# main_board.net
KiCad netlist of a schematic drawn in EAGLE
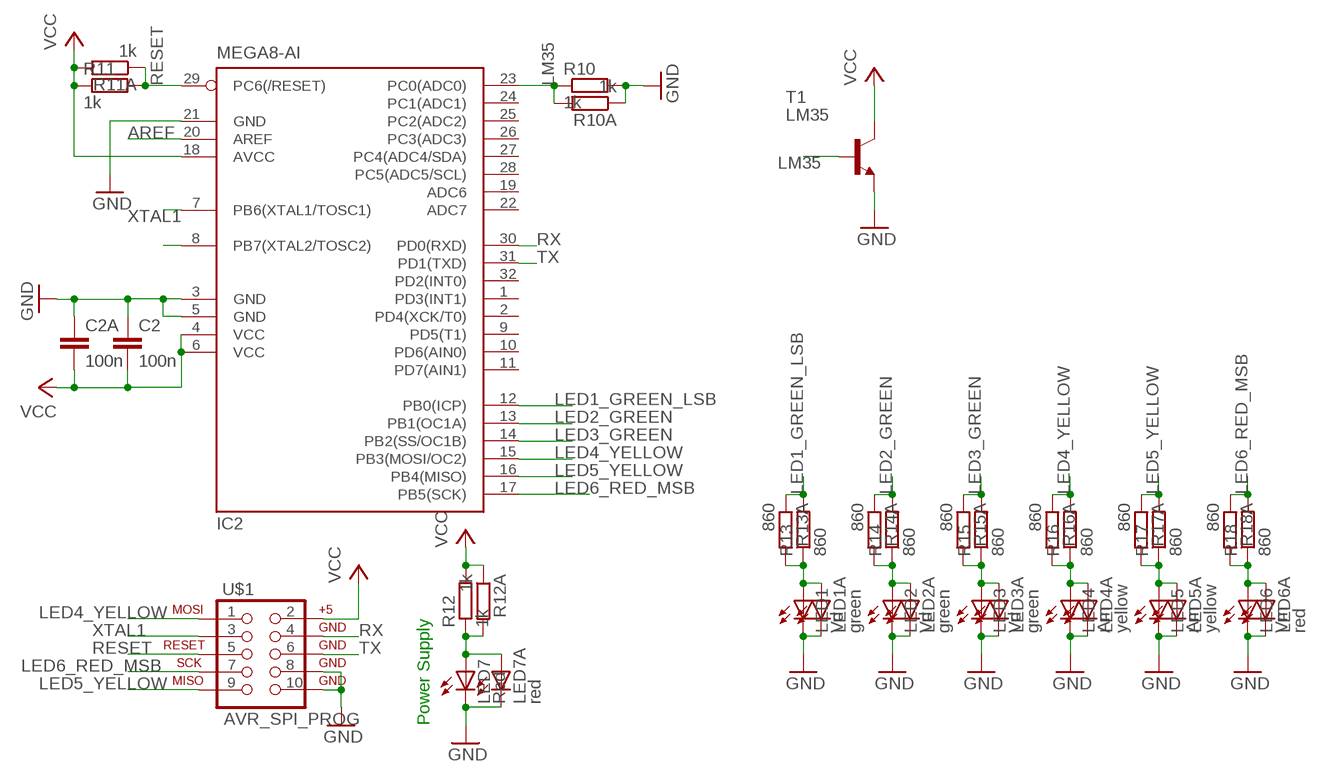
[diagram p0: schematic, sheet 1]

(export (version "E")
  (design (tool "Eeschema 10.0.6"))
  (components
    (comp (ref "C2")
      (value "100n")
      (footprint "eagle-import:C5B3")
      (libsource (lib "eagle-import") (part "C5/3"))
    )
    (comp (ref "C2A")
      (value "100n")
      (footprint "eagle-import:C0805")
      (libsource (lib "eagle-import") (part "C-EUC0805"))
    )
    (comp (ref "IC2")
      (value "MEGA8-AI")
      (footprint "eagle-import:TQFP32-08")
      (fields (field (name "MPN") "ATMEGA8-16AU"))
      (libsource (lib "eagle-import") (part "MEGA8-AI"))
    )
    (comp (ref "LED1")
      (value "Vd")
      (footprint "eagle-import:LED3MM")
      (libsource (lib "eagle-import") (part "LED3MM"))
    )
    (comp (ref "LED1A")
      (value "green")
      (footprint "eagle-import:CHIP-LED0805")
      (libsource (lib "eagle-import") (part "LEDCHIP-LED0805"))
    )
    (comp (ref "LED2")
      (value "Vd")
      (footprint "eagle-import:LED3MM")
      (libsource (lib "eagle-import") (part "LED3MM"))
    )
    (comp (ref "LED2A")
      (value "green")
      (footprint "eagle-import:CHIP-LED0805")
      (libsource (lib "eagle-import") (part "LEDCHIP-LED0805"))
    )
    (comp (ref "LED3")
      (value "Vd")
      (footprint "eagle-import:LED3MM")
      (libsource (lib "eagle-import") (part "LED3MM"))
    )
    (comp (ref "LED3A")
      (value "green")
      (footprint "eagle-import:CHIP-LED0805")
      (libsource (lib "eagle-import") (part "LEDCHIP-LED0805"))
    )
    (comp (ref "LED4")
      (value "Am")
      (footprint "eagle-import:LED3MM")
      (libsource (lib "eagle-import") (part "LED3MM"))
    )
    (comp (ref "LED4A")
      (value "yellow")
      (footprint "eagle-import:CHIP-LED0805")
      (libsource (lib "eagle-import") (part "LEDCHIP-LED0805"))
    )
    (comp (ref "LED5")
      (value "Am")
      (footprint "eagle-import:LED3MM")
      (libsource (lib "eagle-import") (part "LED3MM"))
    )
    (comp (ref "LED5A")
      (value "yellow")
      (footprint "eagle-import:CHIP-LED0805")
      (libsource (lib "eagle-import") (part "LEDCHIP-LED0805"))
    )
    (comp (ref "LED6")
      (value "Vm")
      (footprint "eagle-import:LED3MM")
      (libsource (lib "eagle-import") (part "LED3MM"))
    )
    (comp (ref "LED6A")
      (value "red")
      (footprint "eagle-import:CHIP-LED0805")
      (libsource (lib "eagle-import") (part "LEDCHIP-LED0805"))
    )
    (comp (ref "LED7")
      (value "Red")
      (footprint "eagle-import:LED3MM")
      (libsource (lib "eagle-import") (part "LED3MM"))
    )
    (comp (ref "LED7A")
      (value "red")
      (footprint "eagle-import:CHIP-LED0805")
      (libsource (lib "eagle-import") (part "LEDCHIP-LED0805"))
    )
    (comp (ref "R10")
      (value "1k")
      (footprint "eagle-import:0207_10")
      (libsource (lib "eagle-import") (part "resistor_R-EU_0207/10"))
    )
    (comp (ref "R10A")
      (value "1k")
      (footprint "eagle-import:M0805")
      (libsource (lib "eagle-import") (part "R-EU_M0805"))
    )
    (comp (ref "R11")
      (value "1k")
      (footprint "eagle-import:0207_10")
      (libsource (lib "eagle-import") (part "resistor_R-EU_0207/10"))
    )
    (comp (ref "R11A")
      (value "1k")
      (footprint "eagle-import:M0805")
      (libsource (lib "eagle-import") (part "R-EU_M0805"))
    )
    (comp (ref "R12")
      (value "1k")
      (footprint "eagle-import:0207_10")
      (libsource (lib "eagle-import") (part "resistor_R-EU_0207/10"))
    )
    (comp (ref "R12A")
      (value "1k")
      (footprint "eagle-import:M0805")
      (libsource (lib "eagle-import") (part "R-EU_M0805"))
    )
    (comp (ref "R13")
      (value "860")
      (footprint "eagle-import:0207_10")
      (libsource (lib "eagle-import") (part "resistor_R-EU_0207/10"))
    )
    (comp (ref "R13A")
      (value "860")
      (footprint "eagle-import:M0805")
      (libsource (lib "eagle-import") (part "R-EU_M0805"))
    )
    (comp (ref "R14")
      (value "860")
      (footprint "eagle-import:0207_10")
      (libsource (lib "eagle-import") (part "resistor_R-EU_0207/10"))
    )
    (comp (ref "R14A")
      (value "860")
      (footprint "eagle-import:M0805")
      (libsource (lib "eagle-import") (part "R-EU_M0805"))
    )
    (comp (ref "R15")
      (value "860")
      (footprint "eagle-import:0207_10")
      (libsource (lib "eagle-import") (part "resistor_R-EU_0207/10"))
    )
    (comp (ref "R15A")
      (value "860")
      (footprint "eagle-import:M0805")
      (libsource (lib "eagle-import") (part "R-EU_M0805"))
    )
    (comp (ref "R16")
      (value "860")
      (footprint "eagle-import:0207_10")
      (libsource (lib "eagle-import") (part "resistor_R-EU_0207/10"))
    )
    (comp (ref "R16A")
      (value "860")
      (footprint "eagle-import:M0805")
      (libsource (lib "eagle-import") (part "R-EU_M0805"))
    )
    (comp (ref "R17")
      (value "860")
      (footprint "eagle-import:0207_10")
      (libsource (lib "eagle-import") (part "resistor_R-EU_0207/10"))
    )
    (comp (ref "R17A")
      (value "860")
      (footprint "eagle-import:M0805")
      (libsource (lib "eagle-import") (part "R-EU_M0805"))
    )
    (comp (ref "R18")
      (value "860")
      (footprint "eagle-import:0207_10")
      (libsource (lib "eagle-import") (part "resistor_R-EU_0207/10"))
    )
    (comp (ref "R18A")
      (value "860")
      (footprint "eagle-import:M0805")
      (libsource (lib "eagle-import") (part "R-EU_M0805"))
    )
    (comp (ref "T1")
      (value "LM35")
      (footprint "eagle-import:TO92-CBE")
      (libsource (lib "eagle-import") (part "-NPN-TO92-CBEMPS2222A"))
    )
    (comp (ref "U$1")
      (value "AVR_SPI_PROG")
      (footprint "eagle-import:AVR_ICSP")
      (libsource (lib "eagle-import") (part "AVR_SPI_PROG"))
    )
  )
  (nets
    (net (code "1") (name "/AREF") (class "Default")
      (node (ref "IC2") (pin "20") (pinfunction "AREF_20") (pintype "passive"))
    )
    (net (code "2") (name "/LED1_GREEN_LSB") (class "Default")
      (node (ref "IC2") (pin "12") (pinfunction "PB0(ICP)_12") (pintype "bidirectional"))
      (node (ref "R13") (pin "2") (pinfunction "2_2") (pintype "passive"))
      (node (ref "R13A") (pin "1") (pinfunction "1_1") (pintype "passive"))
    )
    (net (code "3") (name "/LED2_GREEN") (class "Default")
      (node (ref "IC2") (pin "13") (pinfunction "PB1(OC1A)_13") (pintype "bidirectional"))
      (node (ref "R14") (pin "2") (pinfunction "2_2") (pintype "passive"))
      (node (ref "R14A") (pin "1") (pinfunction "1_1") (pintype "passive"))
    )
    (net (code "4") (name "/LED3_GREEN") (class "Default")
      (node (ref "IC2") (pin "14") (pinfunction "PB2(SS/OC1B)_14") (pintype "bidirectional"))
      (node (ref "R15") (pin "2") (pinfunction "2_2") (pintype "passive"))
      (node (ref "R15A") (pin "1") (pinfunction "1_1") (pintype "passive"))
    )
    (net (code "5") (name "/LED4_YELLOW") (class "Default")
      (node (ref "IC2") (pin "15") (pinfunction "PB3(MOSI/OC2)_15") (pintype "bidirectional"))
      (node (ref "R16") (pin "2") (pinfunction "2_2") (pintype "passive"))
      (node (ref "R16A") (pin "1") (pinfunction "1_1") (pintype "passive"))
      (node (ref "U$1") (pin "1") (pinfunction "1_1") (pintype "passive"))
    )
    (net (code "6") (name "/LED5_YELLOW") (class "Default")
      (node (ref "IC2") (pin "16") (pinfunction "PB4(MISO)_16") (pintype "bidirectional"))
      (node (ref "R17") (pin "2") (pinfunction "2_2") (pintype "passive"))
      (node (ref "R17A") (pin "1") (pinfunction "1_1") (pintype "passive"))
      (node (ref "U$1") (pin "9") (pinfunction "9_9") (pintype "passive"))
    )
    (net (code "7") (name "/LED6_RED_MSB") (class "Default")
      (node (ref "IC2") (pin "17") (pinfunction "PB5(SCK)_17") (pintype "bidirectional"))
      (node (ref "R18") (pin "2") (pinfunction "2_2") (pintype "passive"))
      (node (ref "R18A") (pin "1") (pinfunction "1_1") (pintype "passive"))
      (node (ref "U$1") (pin "7") (pinfunction "7_7") (pintype "passive"))
    )
    (net (code "8") (name "/LM35") (class "Default")
      (node (ref "IC2") (pin "23") (pinfunction "PC0(ADC0)_23") (pintype "bidirectional"))
      (node (ref "R10") (pin "1") (pinfunction "1_1") (pintype "passive"))
      (node (ref "R10A") (pin "2") (pinfunction "2_2") (pintype "passive"))
      (node (ref "T1") (pin "B") (pinfunction "B_B") (pintype "passive"))
    )
    (net (code "9") (name "/RESET") (class "Default")
      (node (ref "IC2") (pin "29") (pinfunction "PC6(/RESET)_29") (pintype "bidirectional"))
      (node (ref "R11") (pin "2") (pinfunction "2_2") (pintype "passive"))
      (node (ref "R11A") (pin "1") (pinfunction "1_1") (pintype "passive"))
      (node (ref "U$1") (pin "5") (pinfunction "5_5") (pintype "passive"))
    )
    (net (code "10") (name "/RX") (class "Default")
      (node (ref "IC2") (pin "30") (pinfunction "PD0(RXD)_30") (pintype "bidirectional"))
      (node (ref "U$1") (pin "4") (pinfunction "4_4") (pintype "passive"))
    )
    (net (code "11") (name "/TX") (class "Default")
      (node (ref "IC2") (pin "31") (pinfunction "PD1(TXD)_31") (pintype "bidirectional"))
      (node (ref "U$1") (pin "6") (pinfunction "6_6") (pintype "passive"))
    )
    (net (code "12") (name "/XTAL1") (class "Default")
      (node (ref "IC2") (pin "7") (pinfunction "PB6(XTAL1/TOSC1)_7") (pintype "bidirectional"))
      (node (ref "U$1") (pin "3") (pinfunction "3_3") (pintype "passive"))
    )
    (net (code "13") (name "GND") (class "Default")
      (node (ref "C2") (pin "1") (pinfunction "1_1") (pintype "passive"))
      (node (ref "C2A") (pin "1") (pinfunction "1_1") (pintype "passive"))
      (node (ref "IC2") (pin "21") (pinfunction "GND_21") (pintype "power_in"))
      (node (ref "IC2") (pin "3") (pinfunction "GND_3") (pintype "power_in"))
      (node (ref "IC2") (pin "5") (pinfunction "GND_5") (pintype "power_in"))
      (node (ref "LED1") (pin "K") (pinfunction "C_K") (pintype "passive"))
      (node (ref "LED1A") (pin "C") (pinfunction "C_C") (pintype "passive"))
      (node (ref "LED2") (pin "K") (pinfunction "C_K") (pintype "passive"))
      (node (ref "LED2A") (pin "C") (pinfunction "C_C") (pintype "passive"))
      (node (ref "LED3") (pin "K") (pinfunction "C_K") (pintype "passive"))
      (node (ref "LED3A") (pin "C") (pinfunction "C_C") (pintype "passive"))
      (node (ref "LED4") (pin "K") (pinfunction "C_K") (pintype "passive"))
      (node (ref "LED4A") (pin "C") (pinfunction "C_C") (pintype "passive"))
      (node (ref "LED5") (pin "K") (pinfunction "C_K") (pintype "passive"))
      (node (ref "LED5A") (pin "C") (pinfunction "C_C") (pintype "passive"))
      (node (ref "LED6") (pin "K") (pinfunction "C_K") (pintype "passive"))
      (node (ref "LED6A") (pin "C") (pinfunction "C_C") (pintype "passive"))
      (node (ref "LED7") (pin "K") (pinfunction "C_K") (pintype "passive"))
      (node (ref "LED7A") (pin "C") (pinfunction "C_C") (pintype "passive"))
      (node (ref "R10") (pin "2") (pinfunction "2_2") (pintype "passive"))
      (node (ref "R10A") (pin "1") (pinfunction "1_1") (pintype "passive"))
      (node (ref "T1") (pin "E") (pinfunction "E_E") (pintype "passive"))
      (node (ref "U$1") (pin "10") (pinfunction "10_10") (pintype "passive"))
      (node (ref "U$1") (pin "8") (pinfunction "8_8") (pintype "passive"))
    )
    (net (code "14") (name "Net-(LED1-PadA)") (class "Default")
      (node (ref "LED1") (pin "A") (pinfunction "A_A") (pintype "passive"))
      (node (ref "LED1A") (pin "A") (pinfunction "A_A") (pintype "passive"))
      (node (ref "R13") (pin "1") (pinfunction "1_1") (pintype "passive"))
      (node (ref "R13A") (pin "2") (pinfunction "2_2") (pintype "passive"))
    )
    (net (code "15") (name "Net-(LED2-PadA)") (class "Default")
      (node (ref "LED2") (pin "A") (pinfunction "A_A") (pintype "passive"))
      (node (ref "LED2A") (pin "A") (pinfunction "A_A") (pintype "passive"))
      (node (ref "R14") (pin "1") (pinfunction "1_1") (pintype "passive"))
      (node (ref "R14A") (pin "2") (pinfunction "2_2") (pintype "passive"))
    )
    (net (code "16") (name "Net-(LED3-PadA)") (class "Default")
      (node (ref "LED3") (pin "A") (pinfunction "A_A") (pintype "passive"))
      (node (ref "LED3A") (pin "A") (pinfunction "A_A") (pintype "passive"))
      (node (ref "R15") (pin "1") (pinfunction "1_1") (pintype "passive"))
      (node (ref "R15A") (pin "2") (pinfunction "2_2") (pintype "passive"))
    )
    (net (code "17") (name "Net-(LED4-PadA)") (class "Default")
      (node (ref "LED4") (pin "A") (pinfunction "A_A") (pintype "passive"))
      (node (ref "LED4A") (pin "A") (pinfunction "A_A") (pintype "passive"))
      (node (ref "R16") (pin "1") (pinfunction "1_1") (pintype "passive"))
      (node (ref "R16A") (pin "2") (pinfunction "2_2") (pintype "passive"))
    )
    (net (code "18") (name "Net-(LED5-PadA)") (class "Default")
      (node (ref "LED5") (pin "A") (pinfunction "A_A") (pintype "passive"))
      (node (ref "LED5A") (pin "A") (pinfunction "A_A") (pintype "passive"))
      (node (ref "R17") (pin "1") (pinfunction "1_1") (pintype "passive"))
      (node (ref "R17A") (pin "2") (pinfunction "2_2") (pintype "passive"))
    )
    (net (code "19") (name "Net-(LED6-PadA)") (class "Default")
      (node (ref "LED6") (pin "A") (pinfunction "A_A") (pintype "passive"))
      (node (ref "LED6A") (pin "A") (pinfunction "A_A") (pintype "passive"))
      (node (ref "R18") (pin "1") (pinfunction "1_1") (pintype "passive"))
      (node (ref "R18A") (pin "2") (pinfunction "2_2") (pintype "passive"))
    )
    (net (code "20") (name "Net-(LED7-PadA)") (class "Default")
      (node (ref "LED7") (pin "A") (pinfunction "A_A") (pintype "passive"))
      (node (ref "LED7A") (pin "A") (pinfunction "A_A") (pintype "passive"))
      (node (ref "R12") (pin "1") (pinfunction "1_1") (pintype "passive"))
      (node (ref "R12A") (pin "2") (pinfunction "2_2") (pintype "passive"))
    )
    (net (code "21") (name "VCC") (class "Default")
      (node (ref "C2") (pin "2") (pinfunction "2_2") (pintype "passive"))
      (node (ref "C2A") (pin "2") (pinfunction "2_2") (pintype "passive"))
      (node (ref "IC2") (pin "18") (pinfunction "AVCC_18") (pintype "power_in"))
      (node (ref "IC2") (pin "4") (pinfunction "VCC_4") (pintype "power_in"))
      (node (ref "IC2") (pin "6") (pinfunction "VCC_6") (pintype "power_in"))
      (node (ref "R11") (pin "1") (pinfunction "1_1") (pintype "passive"))
      (node (ref "R11A") (pin "2") (pinfunction "2_2") (pintype "passive"))
      (node (ref "R12") (pin "2") (pinfunction "2_2") (pintype "passive"))
      (node (ref "R12A") (pin "1") (pinfunction "1_1") (pintype "passive"))
      (node (ref "T1") (pin "C") (pinfunction "C_C") (pintype "passive"))
      (node (ref "U$1") (pin "2") (pinfunction "2_2") (pintype "passive"))
    )
    (net (code "22") (name "unconnected-(IC2-ADC6-Pad19)") (class "Default")
      (node (ref "IC2") (pin "19") (pinfunction "ADC6_19") (pintype "bidirectional"))
    )
    (net (code "23") (name "unconnected-(IC2-ADC7-Pad22)") (class "Default")
      (node (ref "IC2") (pin "22") (pinfunction "ADC7_22") (pintype "bidirectional"))
    )
    (net (code "24") (name "unconnected-(IC2-PB7(XTAL2{slash}TOSC2)-Pad8)") (class "Default")
      (node (ref "IC2") (pin "8") (pinfunction "PB7(XTAL2/TOSC2)_8") (pintype "bidirectional"))
    )
    (net (code "25") (name "unconnected-(IC2-PC1(ADC1)-Pad24)") (class "Default")
      (node (ref "IC2") (pin "24") (pinfunction "PC1(ADC1)_24") (pintype "bidirectional"))
    )
    (net (code "26") (name "unconnected-(IC2-PC2(ADC2)-Pad25)") (class "Default")
      (node (ref "IC2") (pin "25") (pinfunction "PC2(ADC2)_25") (pintype "bidirectional"))
    )
    (net (code "27") (name "unconnected-(IC2-PC3(ADC3)-Pad26)") (class "Default")
      (node (ref "IC2") (pin "26") (pinfunction "PC3(ADC3)_26") (pintype "bidirectional"))
    )
    (net (code "28") (name "unconnected-(IC2-PC4(ADC4{slash}SDA)-Pad27)") (class "Default")
      (node (ref "IC2") (pin "27") (pinfunction "PC4(ADC4/SDA)_27") (pintype "bidirectional"))
    )
    (net (code "29") (name "unconnected-(IC2-PC5(ADC5{slash}SCL)-Pad28)") (class "Default")
      (node (ref "IC2") (pin "28") (pinfunction "PC5(ADC5/SCL)_28") (pintype "bidirectional"))
    )
    (net (code "30") (name "unconnected-(IC2-PD2(INT0)-Pad32)") (class "Default")
      (node (ref "IC2") (pin "32") (pinfunction "PD2(INT0)_32") (pintype "bidirectional"))
    )
    (net (code "31") (name "unconnected-(IC2-PD3(INT1)-Pad1)") (class "Default")
      (node (ref "IC2") (pin "1") (pinfunction "PD3(INT1)_1") (pintype "bidirectional"))
    )
    (net (code "32") (name "unconnected-(IC2-PD4(XCK{slash}T0)-Pad2)") (class "Default")
      (node (ref "IC2") (pin "2") (pinfunction "PD4(XCK/T0)_2") (pintype "bidirectional"))
    )
    (net (code "33") (name "unconnected-(IC2-PD5(T1)-Pad9)") (class "Default")
      (node (ref "IC2") (pin "9") (pinfunction "PD5(T1)_9") (pintype "bidirectional"))
    )
    (net (code "34") (name "unconnected-(IC2-PD6(AIN0)-Pad10)") (class "Default")
      (node (ref "IC2") (pin "10") (pinfunction "PD6(AIN0)_10") (pintype "bidirectional"))
    )
    (net (code "35") (name "unconnected-(IC2-PD7(AIN1)-Pad11)") (class "Default")
      (node (ref "IC2") (pin "11") (pinfunction "PD7(AIN1)_11") (pintype "bidirectional"))
    )
  )
)
